# splitter.net
KiCad netlist of a schematic drawn in EAGLE
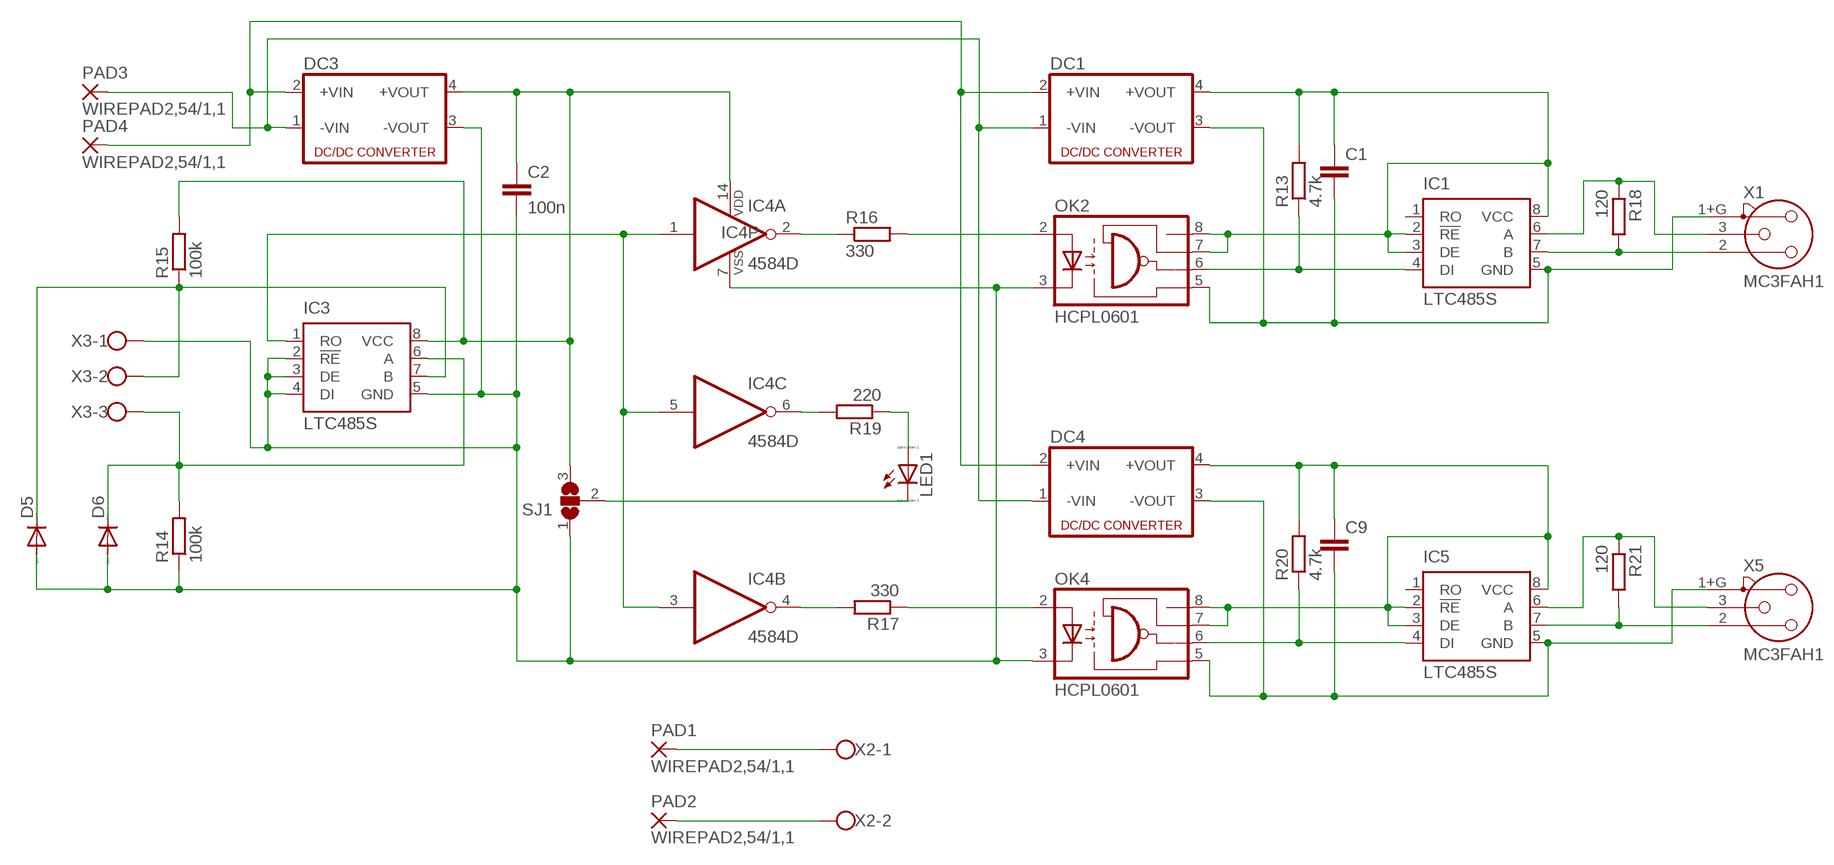
[diagram p0: schematic, sheet 1]

(export (version "E")
  (design (tool "Eeschema 10.0.6"))
  (components
    (comp (ref "C1")
      (value "C-EUC1206K")
      (footprint "eagle-import:C1206K")
      (libsource (lib "eagle-import") (part "C-EUC1206K"))
    )
    (comp (ref "C2")
      (value "100n")
      (footprint "eagle-import:C1206K")
      (libsource (lib "eagle-import") (part "C-EUC1206K"))
    )
    (comp (ref "C9")
      (value "C-EUC1206K")
      (footprint "eagle-import:C1206K")
      (libsource (lib "eagle-import") (part "C-EUC1206K"))
    )
    (comp (ref "D5")
      (value "DIODE-SOD80C")
      (footprint "eagle-import:SOD80C")
      (libsource (lib "eagle-import") (part "DIODE-SOD80C"))
    )
    (comp (ref "D6")
      (value "DIODE-SOD80C")
      (footprint "eagle-import:SOD80C")
      (libsource (lib "eagle-import") (part "DIODE-SOD80C"))
    )
    (comp (ref "DC1")
      (value "NME")
      (footprint "eagle-import:NME")
      (fields (field (name "MF") "C & D TECHNOLOGIES, INC") (field (name "MPN") "NME1205D"))
      (libsource (lib "eagle-import") (part "NME"))
    )
    (comp (ref "DC3")
      (value "NME")
      (footprint "eagle-import:NME")
      (fields (field (name "MF") "C & D TECHNOLOGIES, INC") (field (name "MPN") "NME1205D"))
      (libsource (lib "eagle-import") (part "NME"))
    )
    (comp (ref "DC4")
      (value "NME")
      (footprint "eagle-import:NME")
      (fields (field (name "MF") "C & D TECHNOLOGIES, INC") (field (name "MPN") "NME1205D"))
      (libsource (lib "eagle-import") (part "NME"))
    )
    (comp (ref "IC1")
      (value "LTC485S")
      (footprint "eagle-import:SOIC8")
      (libsource (lib "eagle-import") (part "LTC485S"))
    )
    (comp (ref "IC3")
      (value "LTC485S")
      (footprint "eagle-import:SOIC8")
      (libsource (lib "eagle-import") (part "LTC485S"))
    )
    (comp (ref "IC4")
      (value "4584D")
      (footprint "eagle-import:SO14")
      (libsource (lib "eagle-import") (part "4584D"))
    )
    (comp (ref "IC5")
      (value "LTC485S")
      (footprint "eagle-import:SOIC8")
      (libsource (lib "eagle-import") (part "LTC485S"))
    )
    (comp (ref "LED1")
      (value "LED_E")
      (footprint "eagle-import:LED_1206")
      (libsource (lib "eagle-import") (part "LED_E"))
    )
    (comp (ref "OK2")
      (value "HCPL0601")
      (footprint "eagle-import:SOIC08")
      (fields (field (name "MF") "AGILENT TECHNOLOGIES") (field (name "MPN") "HCPL-0601-000E"))
      (libsource (lib "eagle-import") (part "HCPL0601"))
    )
    (comp (ref "OK4")
      (value "HCPL0601")
      (footprint "eagle-import:SOIC08")
      (fields (field (name "MF") "AGILENT TECHNOLOGIES") (field (name "MPN") "HCPL-0601-000E"))
      (libsource (lib "eagle-import") (part "HCPL0601"))
    )
    (comp (ref "PAD1")
      (value "WIREPAD2,54/1,1")
      (footprint "eagle-import:2,54_1,1")
      (libsource (lib "eagle-import") (part "WIREPAD2,54/1,1"))
    )
    (comp (ref "PAD2")
      (value "WIREPAD2,54/1,1")
      (footprint "eagle-import:2,54_1,1")
      (libsource (lib "eagle-import") (part "WIREPAD2,54/1,1"))
    )
    (comp (ref "PAD3")
      (value "WIREPAD2,54/1,1")
      (footprint "eagle-import:2,54_1,1")
      (libsource (lib "eagle-import") (part "WIREPAD2,54/1,1"))
    )
    (comp (ref "PAD4")
      (value "WIREPAD2,54/1,1")
      (footprint "eagle-import:2,54_1,1")
      (libsource (lib "eagle-import") (part "WIREPAD2,54/1,1"))
    )
    (comp (ref "R13")
      (value "4.7k")
      (footprint "eagle-import:M1206")
      (libsource (lib "eagle-import") (part "R-EU_M1206"))
    )
    (comp (ref "R14")
      (value "100k")
      (footprint "eagle-import:M1206")
      (libsource (lib "eagle-import") (part "R-EU_M1206"))
    )
    (comp (ref "R15")
      (value "100k")
      (footprint "eagle-import:M1206")
      (libsource (lib "eagle-import") (part "R-EU_M1206"))
    )
    (comp (ref "R16")
      (value "330")
      (footprint "eagle-import:M1206")
      (libsource (lib "eagle-import") (part "R-EU_M1206"))
    )
    (comp (ref "R17")
      (value "330")
      (footprint "eagle-import:M1206")
      (libsource (lib "eagle-import") (part "R-EU_M1206"))
    )
    (comp (ref "R18")
      (value "120")
      (footprint "eagle-import:M1206")
      (libsource (lib "eagle-import") (part "R-EU_M1206"))
    )
    (comp (ref "R19")
      (value "220")
      (footprint "eagle-import:M1206")
      (libsource (lib "eagle-import") (part "R-EU_M1206"))
    )
    (comp (ref "R20")
      (value "4.7k")
      (footprint "eagle-import:M1206")
      (libsource (lib "eagle-import") (part "R-EU_M1206"))
    )
    (comp (ref "R21")
      (value "120")
      (footprint "eagle-import:M1206")
      (libsource (lib "eagle-import") (part "R-EU_M1206"))
    )
    (comp (ref "SJ1")
      (value "SJ2W")
      (footprint "eagle-import:SJ_2")
      (libsource (lib "eagle-import") (part "SJ2W"))
    )
    (comp (ref "X1")
      (value "MC3FAH1")
      (footprint "eagle-import:NC3FAH1")
      (libsource (lib "eagle-import") (part "MC3?FAH1"))
    )
    (comp (ref "X2")
      (value "W237-102")
      (footprint "eagle-import:W237-102")
      (fields (field (name "MPN") "237-102"))
      (libsource (lib "eagle-import") (part "W237-102"))
    )
    (comp (ref "X3")
      (value "W237-103")
      (footprint "eagle-import:W237-103")
      (fields (field (name "MPN") "237-103"))
      (libsource (lib "eagle-import") (part "W237-103"))
    )
    (comp (ref "X5")
      (value "MC3FAH1")
      (footprint "eagle-import:NC3FAH1")
      (libsource (lib "eagle-import") (part "MC3?FAH1"))
    )
  )
  (nets
    (net (code "1") (name "Net-(DC1-+VIN)") (class "Default")
      (node (ref "DC1") (pin "2") (pinfunction "+VIN_2") (pintype "passive"))
      (node (ref "DC3") (pin "2") (pinfunction "+VIN_2") (pintype "passive"))
      (node (ref "DC4") (pin "2") (pinfunction "+VIN_2") (pintype "passive"))
      (node (ref "PAD4") (pin "1") (pinfunction "P_1") (pintype "passive"))
    )
    (net (code "2") (name "Net-(DC1-+VOUT)") (class "Default")
      (node (ref "C1") (pin "1") (pinfunction "1_1") (pintype "passive"))
      (node (ref "DC1") (pin "4") (pinfunction "+VOUT_4") (pintype "passive"))
      (node (ref "IC1") (pin "2") (pinfunction "~{RE}_2") (pintype "input"))
      (node (ref "IC1") (pin "3") (pinfunction "DE_3") (pintype "input"))
      (node (ref "IC1") (pin "8") (pinfunction "VCC_8") (pintype "input"))
      (node (ref "OK2") (pin "7") (pinfunction "VE_7") (pintype "passive"))
      (node (ref "OK2") (pin "8") (pinfunction "VCC_8") (pintype "passive"))
      (node (ref "R13") (pin "2") (pinfunction "2_2") (pintype "passive"))
    )
    (net (code "3") (name "Net-(DC1--VIN)") (class "Default")
      (node (ref "DC1") (pin "1") (pinfunction "-VIN_1") (pintype "passive"))
      (node (ref "DC3") (pin "1") (pinfunction "-VIN_1") (pintype "passive"))
      (node (ref "DC4") (pin "1") (pinfunction "-VIN_1") (pintype "passive"))
      (node (ref "PAD3") (pin "1") (pinfunction "P_1") (pintype "passive"))
    )
    (net (code "4") (name "Net-(DC1--VOUT)") (class "Default")
      (node (ref "C1") (pin "2") (pinfunction "2_2") (pintype "passive"))
      (node (ref "DC1") (pin "3") (pinfunction "-VOUT_3") (pintype "passive"))
      (node (ref "IC1") (pin "5") (pinfunction "GND_5") (pintype "input"))
      (node (ref "OK2") (pin "5") (pinfunction "GND_5") (pintype "passive"))
      (node (ref "X1") (pin "1+G") (pinfunction "1_1+G") (pintype "passive"))
    )
    (net (code "5") (name "Net-(DC3-+VOUT)") (class "Default")
      (node (ref "C2") (pin "1") (pinfunction "1_1") (pintype "passive"))
      (node (ref "DC3") (pin "4") (pinfunction "+VOUT_4") (pintype "passive"))
      (node (ref "IC3") (pin "8") (pinfunction "VCC_8") (pintype "input"))
      (node (ref "IC4") (pin "14") (pinfunction "VDD_14") (pintype "power_in"))
      (node (ref "R15") (pin "2") (pinfunction "2_2") (pintype "passive"))
      (node (ref "SJ1") (pin "3") (pinfunction "3_3") (pintype "passive"))
    )
    (net (code "6") (name "Net-(DC3--VOUT)") (class "Default")
      (node (ref "C2") (pin "2") (pinfunction "2_2") (pintype "passive"))
      (node (ref "D5") (pin "A") (pinfunction "A_A") (pintype "passive"))
      (node (ref "D6") (pin "A") (pinfunction "A_A") (pintype "passive"))
      (node (ref "DC3") (pin "3") (pinfunction "-VOUT_3") (pintype "passive"))
      (node (ref "IC3") (pin "2") (pinfunction "~{RE}_2") (pintype "input"))
      (node (ref "IC3") (pin "3") (pinfunction "DE_3") (pintype "input"))
      (node (ref "IC3") (pin "4") (pinfunction "DI_4") (pintype "input"))
      (node (ref "IC3") (pin "5") (pinfunction "GND_5") (pintype "input"))
      (node (ref "IC4") (pin "7") (pinfunction "VSS_7") (pintype "power_in"))
      (node (ref "OK2") (pin "3") (pinfunction "C_3") (pintype "passive"))
      (node (ref "OK4") (pin "3") (pinfunction "C_3") (pintype "passive"))
      (node (ref "R14") (pin "1") (pinfunction "1_1") (pintype "passive"))
      (node (ref "SJ1") (pin "1") (pinfunction "1_1") (pintype "passive"))
      (node (ref "X3") (pin "1") (pinfunction "KL_1") (pintype "passive"))
    )
    (net (code "7") (name "Net-(DC4-+VOUT)") (class "Default")
      (node (ref "C9") (pin "1") (pinfunction "1_1") (pintype "passive"))
      (node (ref "DC4") (pin "4") (pinfunction "+VOUT_4") (pintype "passive"))
      (node (ref "IC5") (pin "2") (pinfunction "~{RE}_2") (pintype "input"))
      (node (ref "IC5") (pin "3") (pinfunction "DE_3") (pintype "input"))
      (node (ref "IC5") (pin "8") (pinfunction "VCC_8") (pintype "input"))
      (node (ref "OK4") (pin "7") (pinfunction "VE_7") (pintype "passive"))
      (node (ref "OK4") (pin "8") (pinfunction "VCC_8") (pintype "passive"))
      (node (ref "R20") (pin "2") (pinfunction "2_2") (pintype "passive"))
    )
    (net (code "8") (name "Net-(DC4--VOUT)") (class "Default")
      (node (ref "C9") (pin "2") (pinfunction "2_2") (pintype "passive"))
      (node (ref "DC4") (pin "3") (pinfunction "-VOUT_3") (pintype "passive"))
      (node (ref "IC5") (pin "5") (pinfunction "GND_5") (pintype "input"))
      (node (ref "OK4") (pin "5") (pinfunction "GND_5") (pintype "passive"))
      (node (ref "X5") (pin "1+G") (pinfunction "1_1+G") (pintype "passive"))
    )
    (net (code "9") (name "Net-(IC1-A)") (class "Default")
      (node (ref "IC1") (pin "6") (pinfunction "A_6") (pintype "bidirectional"))
      (node (ref "R18") (pin "1") (pinfunction "1_1") (pintype "passive"))
      (node (ref "X1") (pin "3") (pinfunction "3_3") (pintype "passive"))
    )
    (net (code "10") (name "Net-(IC1-B)") (class "Default")
      (node (ref "IC1") (pin "7") (pinfunction "B_7") (pintype "bidirectional"))
      (node (ref "R18") (pin "2") (pinfunction "2_2") (pintype "passive"))
      (node (ref "X1") (pin "2") (pinfunction "2_2") (pintype "passive"))
    )
    (net (code "11") (name "Net-(IC1-DI)") (class "Default")
      (node (ref "IC1") (pin "4") (pinfunction "DI_4") (pintype "input"))
      (node (ref "OK2") (pin "6") (pinfunction "VO_6") (pintype "passive"))
      (node (ref "R13") (pin "1") (pinfunction "1_1") (pintype "passive"))
    )
    (net (code "12") (name "Net-(IC3-A)") (class "Default")
      (node (ref "D6") (pin "C") (pinfunction "C_C") (pintype "passive"))
      (node (ref "IC3") (pin "6") (pinfunction "A_6") (pintype "bidirectional"))
      (node (ref "R14") (pin "2") (pinfunction "2_2") (pintype "passive"))
      (node (ref "X3") (pin "3") (pinfunction "KL_3") (pintype "passive"))
    )
    (net (code "13") (name "Net-(IC3-B)") (class "Default")
      (node (ref "D5") (pin "C") (pinfunction "C_C") (pintype "passive"))
      (node (ref "IC3") (pin "7") (pinfunction "B_7") (pintype "bidirectional"))
      (node (ref "R15") (pin "1") (pinfunction "1_1") (pintype "passive"))
      (node (ref "X3") (pin "2") (pinfunction "KL_2") (pintype "passive"))
    )
    (net (code "14") (name "Net-(IC3-RO)") (class "Default")
      (node (ref "IC3") (pin "1") (pinfunction "RO_1") (pintype "output"))
      (node (ref "IC4") (pin "1") (pinfunction "I_1") (pintype "input"))
      (node (ref "IC4") (pin "3") (pinfunction "I_3") (pintype "input"))
      (node (ref "IC4") (pin "5") (pinfunction "I_5") (pintype "input"))
    )
    (net (code "15") (name "Net-(IC4A-O)") (class "Default")
      (node (ref "IC4") (pin "2") (pinfunction "O_2") (pintype "output"))
      (node (ref "R16") (pin "1") (pinfunction "1_1") (pintype "passive"))
    )
    (net (code "16") (name "Net-(IC4B-O)") (class "Default")
      (node (ref "IC4") (pin "4") (pinfunction "O_4") (pintype "output"))
      (node (ref "R17") (pin "2") (pinfunction "2_2") (pintype "passive"))
    )
    (net (code "17") (name "Net-(IC4C-O)") (class "Default")
      (node (ref "IC4") (pin "6") (pinfunction "O_6") (pintype "output"))
      (node (ref "R19") (pin "2") (pinfunction "2_2") (pintype "passive"))
    )
    (net (code "18") (name "Net-(IC5-A)") (class "Default")
      (node (ref "IC5") (pin "6") (pinfunction "A_6") (pintype "bidirectional"))
      (node (ref "R21") (pin "1") (pinfunction "1_1") (pintype "passive"))
      (node (ref "X5") (pin "3") (pinfunction "3_3") (pintype "passive"))
    )
    (net (code "19") (name "Net-(IC5-B)") (class "Default")
      (node (ref "IC5") (pin "7") (pinfunction "B_7") (pintype "bidirectional"))
      (node (ref "R21") (pin "2") (pinfunction "2_2") (pintype "passive"))
      (node (ref "X5") (pin "2") (pinfunction "2_2") (pintype "passive"))
    )
    (net (code "20") (name "Net-(IC5-DI)") (class "Default")
      (node (ref "IC5") (pin "4") (pinfunction "DI_4") (pintype "input"))
      (node (ref "OK4") (pin "6") (pinfunction "VO_6") (pintype "passive"))
      (node (ref "R20") (pin "1") (pinfunction "1_1") (pintype "passive"))
    )
    (net (code "21") (name "Net-(LED1-PadA)") (class "Default")
      (node (ref "LED1") (pin "A") (pinfunction "A_A") (pintype "passive"))
      (node (ref "R19") (pin "1") (pinfunction "1_1") (pintype "passive"))
    )
    (net (code "22") (name "Net-(LED1-PadC)") (class "Default")
      (node (ref "LED1") (pin "C") (pinfunction "C_C") (pintype "passive"))
      (node (ref "SJ1") (pin "2") (pinfunction "2_2") (pintype "passive"))
    )
    (net (code "23") (name "Net-(OK2-A)") (class "Default")
      (node (ref "OK2") (pin "2") (pinfunction "A_2") (pintype "passive"))
      (node (ref "R16") (pin "2") (pinfunction "2_2") (pintype "passive"))
    )
    (net (code "24") (name "Net-(OK4-A)") (class "Default")
      (node (ref "OK4") (pin "2") (pinfunction "A_2") (pintype "passive"))
      (node (ref "R17") (pin "1") (pinfunction "1_1") (pintype "passive"))
    )
    (net (code "25") (name "Net-(PAD1-P)") (class "Default")
      (node (ref "PAD1") (pin "1") (pinfunction "P_1") (pintype "passive"))
      (node (ref "X2") (pin "1") (pinfunction "KL_1") (pintype "passive"))
    )
    (net (code "26") (name "Net-(PAD2-P)") (class "Default")
      (node (ref "PAD2") (pin "1") (pinfunction "P_1") (pintype "passive"))
      (node (ref "X2") (pin "2") (pinfunction "KL_2") (pintype "passive"))
    )
    (net (code "27") (name "unconnected-(IC1-RO-Pad1)") (class "Default")
      (node (ref "IC1") (pin "1") (pinfunction "RO_1") (pintype "output"))
    )
    (net (code "28") (name "unconnected-(IC5-RO-Pad1)") (class "Default")
      (node (ref "IC5") (pin "1") (pinfunction "RO_1") (pintype "output"))
    )
  )
)
